# Main.net
KiCad netlist of a schematic drawn in Altium Designer
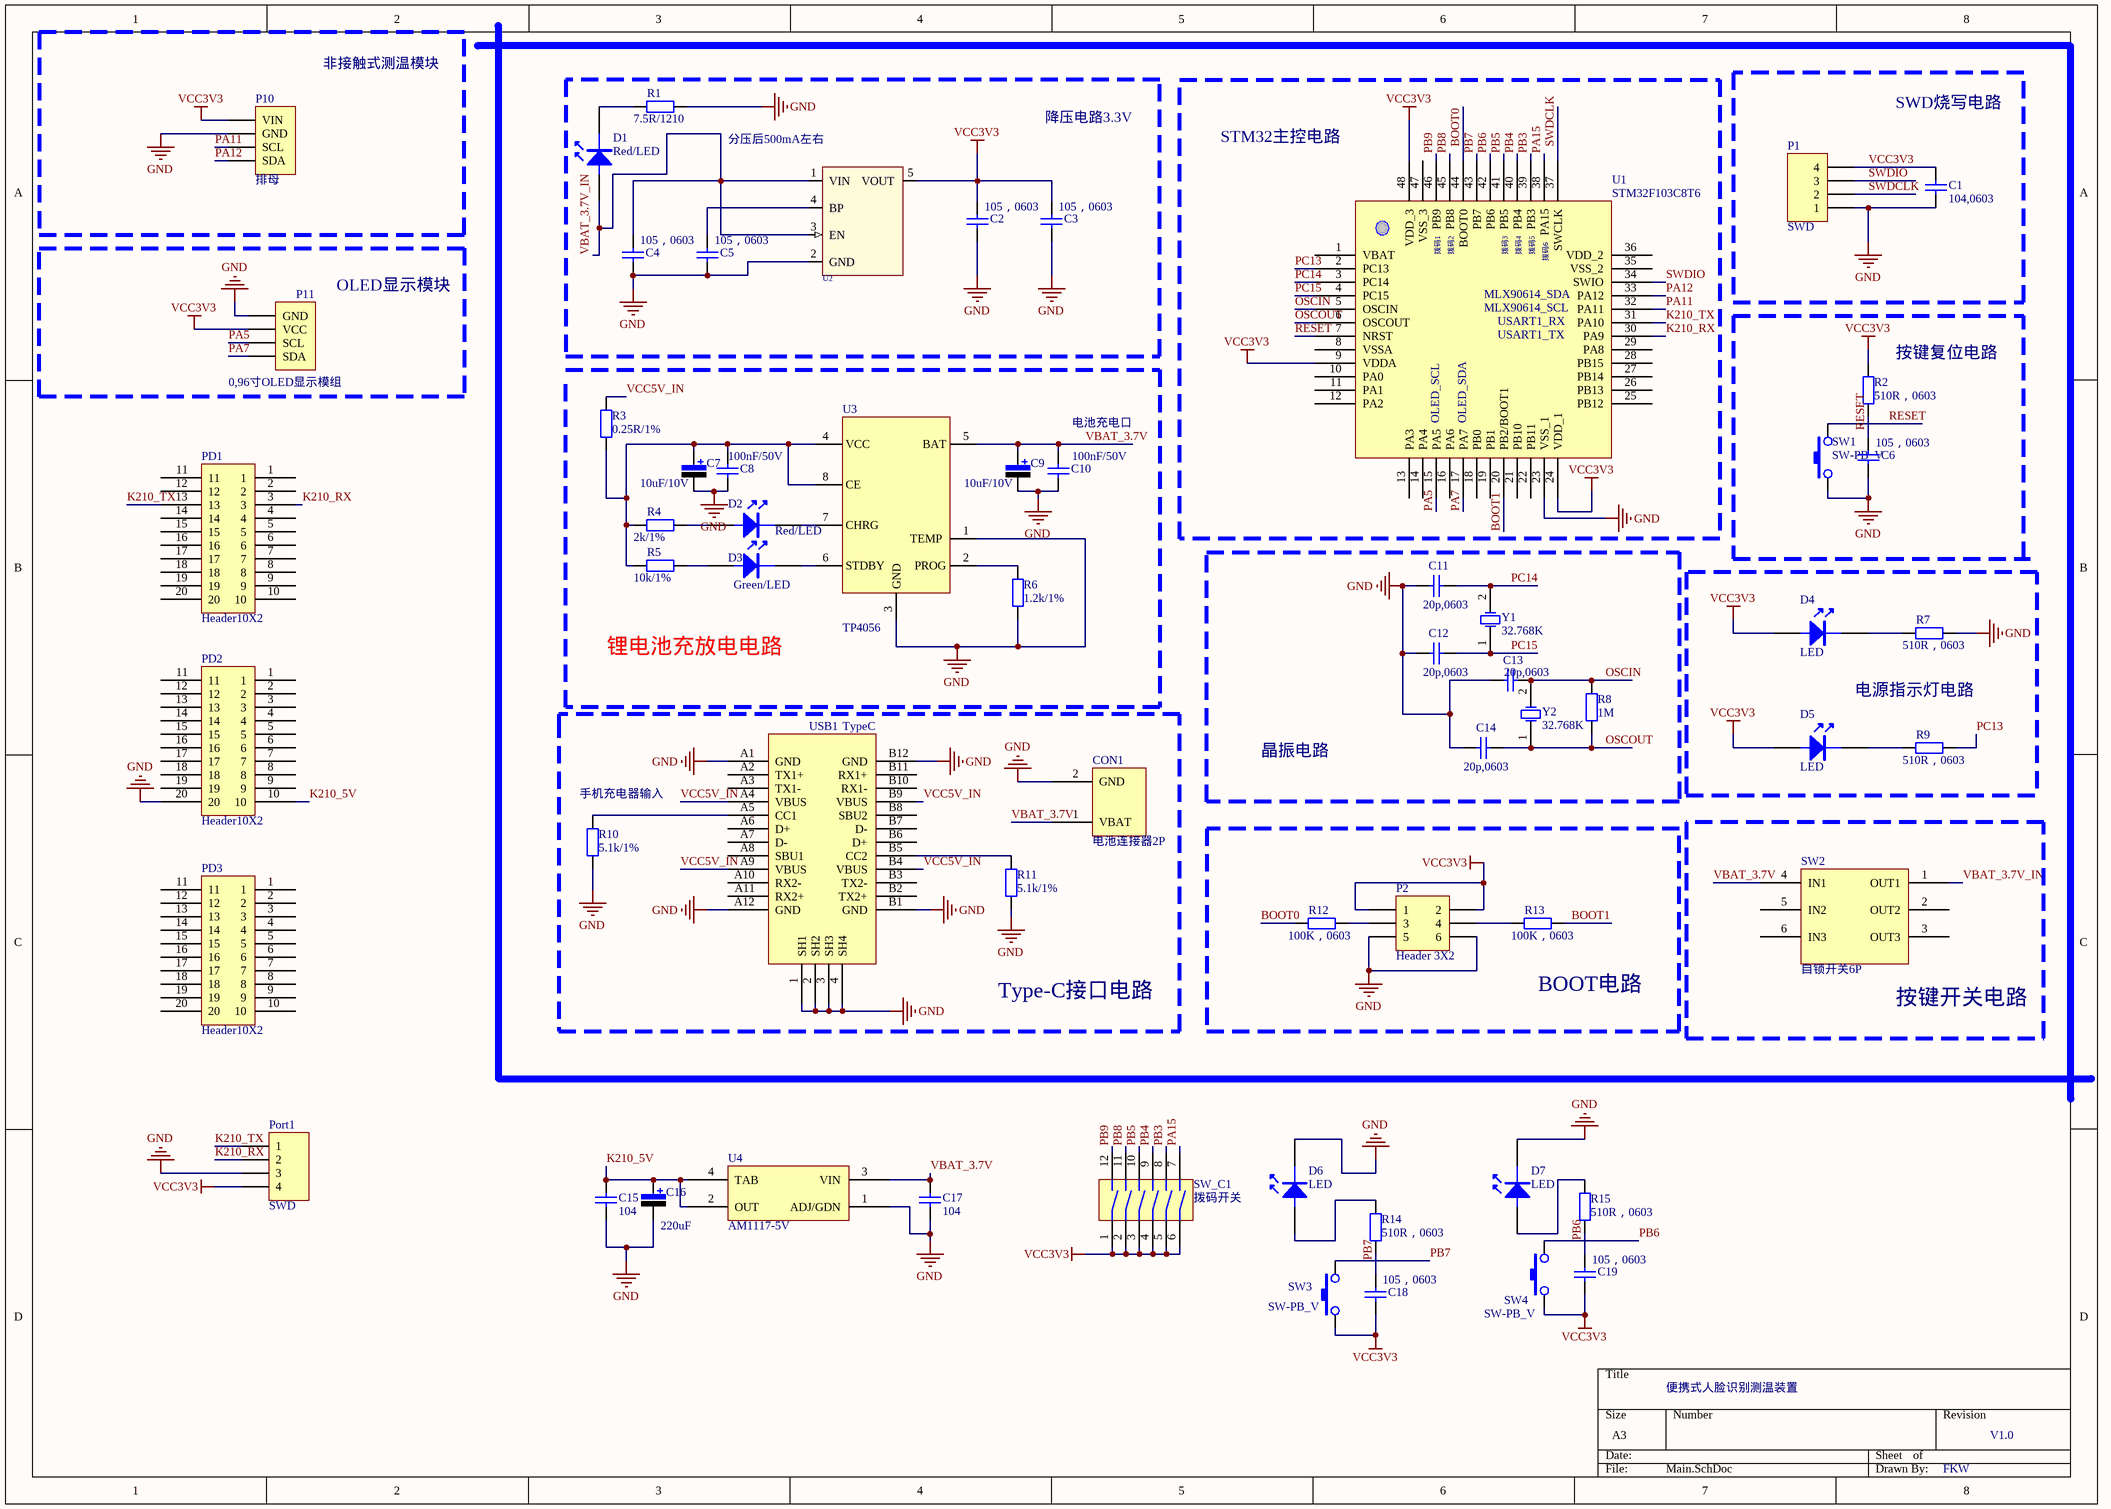
[diagram p0: Main.SchDoc]

(export (version "E")
  (design (tool "Eeschema 10.0.6"))
  (components
    (comp (ref "C1")
      (value "104,0603")
      (footprint "STM32F103C8T6核心板:C0603")
      (description "Capacitor")
      (fields (field (name "PUBLISHER") "Altium Limited"))
      (libsource (lib "STM32F103C8T6") (part "Cap"))
    )
    (comp (ref "C2")
      (value "105，0603")
      (footprint "STM32F103C8T6核心板:C0603")
      (description "Capacitor")
      (fields (field (name "PUBLISHER") "Altium Limited"))
      (libsource (lib "STM32F103C8T6") (part "Cap"))
    )
    (comp (ref "C3")
      (value "105，0603")
      (footprint "STM32F103C8T6核心板:C0603")
      (description "Capacitor")
      (fields (field (name "PUBLISHER") "Altium Limited"))
      (libsource (lib "STM32F103C8T6") (part "Cap"))
    )
    (comp (ref "C4")
      (value "105，0603")
      (footprint "STM32F103C8T6核心板:C0603")
      (description "Capacitor")
      (fields (field (name "PUBLISHER") "Altium Limited"))
      (libsource (lib "STM32F103C8T6") (part "Cap"))
    )
    (comp (ref "C5")
      (value "105，0603")
      (footprint "STM32F103C8T6核心板:C0603")
      (description "Capacitor")
      (fields (field (name "PUBLISHER") "Altium Limited"))
      (libsource (lib "STM32F103C8T6") (part "Cap"))
    )
    (comp (ref "C6")
      (value "105，0603")
      (footprint "STM32F103C8T6核心板:C0603")
      (description "Capacitor")
      (fields (field (name "PUBLISHER") "Altium Limited"))
      (libsource (lib "STM32F103C8T6") (part "Cap"))
    )
    (comp (ref "C7")
      (value "10uF/10V")
      (footprint "C0805tan")
      (libsource (lib "STM32F103C8T6") (part "Cap_电解电容"))
    )
    (comp (ref "C8")
      (value "100nF/50V")
      (footprint "STM32F103C8T6核心板:C0603")
      (description "Capacitor")
      (fields (field (name "PUBLISHER") "Altium Limited"))
      (libsource (lib "STM32F103C8T6") (part "Cap"))
    )
    (comp (ref "C9")
      (value "10uF/10V")
      (footprint "C0805tan")
      (libsource (lib "STM32F103C8T6") (part "Cap_电解电容"))
    )
    (comp (ref "C10")
      (value "100nF/50V")
      (footprint "STM32F103C8T6核心板:C0603")
      (description "Capacitor")
      (fields (field (name "PUBLISHER") "Altium Limited"))
      (libsource (lib "STM32F103C8T6") (part "Cap"))
    )
    (comp (ref "C11")
      (value "20p,0603")
      (footprint "STM32F103C8T6核心板:C0603")
      (description "Capacitor")
      (fields (field (name "PUBLISHER") "Altium Limited"))
      (libsource (lib "STM32F103C8T6") (part "Cap"))
    )
    (comp (ref "C12")
      (value "20p,0603")
      (footprint "STM32F103C8T6核心板:C0603")
      (description "Capacitor")
      (fields (field (name "PUBLISHER") "Altium Limited"))
      (libsource (lib "STM32F103C8T6") (part "Cap"))
    )
    (comp (ref "C13")
      (value "20p,0603")
      (footprint "STM32F103C8T6核心板:C0603")
      (description "Capacitor")
      (fields (field (name "PUBLISHER") "Altium Limited"))
      (libsource (lib "STM32F103C8T6") (part "Cap"))
    )
    (comp (ref "C14")
      (value "20p,0603")
      (footprint "STM32F103C8T6核心板:C0603")
      (description "Capacitor")
      (fields (field (name "PUBLISHER") "Altium Limited"))
      (libsource (lib "STM32F103C8T6") (part "Cap"))
    )
    (comp (ref "C15")
      (value "104")
      (footprint "STM32F103C8T6核心板:C0603")
      (description "Capacitor")
      (fields (field (name "PUBLISHER") "Altium Limited"))
      (libsource (lib "STM32F103C8T6") (part "Cap"))
    )
    (comp (ref "C16")
      (value "220uF")
      (footprint "C0805tan")
      (libsource (lib "STM32F103C8T6") (part "Cap_电解电容"))
    )
    (comp (ref "C17")
      (value "104")
      (footprint "STM32F103C8T6核心板:C0603")
      (description "Capacitor")
      (fields (field (name "PUBLISHER") "Altium Limited"))
      (libsource (lib "STM32F103C8T6") (part "Cap"))
    )
    (comp (ref "C18")
      (value "105，0603")
      (footprint "STM32F103C8T6核心板:C0603")
      (description "Capacitor")
      (fields (field (name "PUBLISHER") "Altium Limited"))
      (libsource (lib "STM32F103C8T6") (part "Cap"))
    )
    (comp (ref "C19")
      (value "105，0603")
      (footprint "STM32F103C8T6核心板:C0603")
      (description "Capacitor")
      (fields (field (name "PUBLISHER") "Altium Limited"))
      (libsource (lib "STM32F103C8T6") (part "Cap"))
    )
    (comp (ref "CON1")
      (value "电池连接器2P")
      (footprint "STM32F103C8T6核心板:CONN-TH_DF1B-2P-2.5DSA-01")
      (description "电池（带防呆口）")
      (libsource (lib "STM32F103C8T6") (part "BATinput_Connector"))
    )
    (comp (ref "D1") (value "Red/LED") (footprint "LED") (libsource (lib "STM32F103C8T6") (part "LED")))
    (comp (ref "D2") (value "Red/LED") (footprint "LED") (libsource (lib "STM32F103C8T6") (part "LED")))
    (comp (ref "D3") (value "Green/LED") (footprint "LED") (libsource (lib "STM32F103C8T6") (part "LED")))
    (comp (ref "D4") (value "LED") (footprint "LED") (libsource (lib "STM32F103C8T6") (part "LED")))
    (comp (ref "D5") (value "LED") (footprint "LED") (libsource (lib "STM32F103C8T6") (part "LED")))
    (comp (ref "D6") (value "LED") (footprint "LED") (libsource (lib "STM32F103C8T6") (part "LED")))
    (comp (ref "D7") (value "LED") (footprint "LED") (libsource (lib "STM32F103C8T6") (part "LED")))
    (comp (ref "P1")
      (value "SWD")
      (footprint "HDR1X4H")
      (description "Header, 4-Pin")
      (fields (field (name "PUBLISHER") "Altium Limited"))
      (libsource (lib "") (part "Header 4_1"))
    )
    (comp (ref "P2")
      (value "Header 3X2")
      (footprint "STM32F103C8T6核心板:HDR2X3")
      (description "Header, 3-Pin, Dual row")
      (fields (field (name "PUBLISHER") "Altium Limited"))
      (libsource (lib "STM32F103C8T6") (part "Header 3X2"))
    )
    (comp (ref "P10") (value "排母") (footprint "HRD1X4") (libsource (lib "STM32F103C8T6") (part "MLX90614")))
    (comp (ref "P11")
      (value "0,96寸OLED显示模组")
      (footprint "STM32F103C8T6核心板:0.96寸OLED显示模组")
      (libsource (lib "STM32F103C8T6") (part "0,96寸OLED显示模组"))
    )
    (comp (ref "PD1")
      (value "Header10X2")
      (footprint "header2X10")
      (libsource (lib "STM32F103C8T6") (part "Header10X2"))
    )
    (comp (ref "PD2")
      (value "Header10X2")
      (footprint "header2X10")
      (libsource (lib "STM32F103C8T6") (part "Header10X2"))
    )
    (comp (ref "PD3")
      (value "Header10X2")
      (footprint "header2X10")
      (libsource (lib "STM32F103C8T6") (part "Header10X2"))
    )
    (comp (ref "Port1")
      (value "SWD")
      (footprint "HDR1X4H")
      (description "Header, 4-Pin")
      (fields (field (name "PUBLISHER") "Altium Limited"))
      (libsource (lib "STM32F103C8T6") (part "Header 4"))
    )
    (comp (ref "R1")
      (value "7.5R/1210")
      (footprint "R0603")
      (description "Resistor")
      (fields (field (name "PUBLISHER") "Altium Limited"))
      (libsource (lib "STM32F103C8T6") (part "Res2"))
    )
    (comp (ref "R2")
      (value "510R，0603")
      (footprint "R0603")
      (description "Resistor")
      (fields (field (name "PUBLISHER") "Altium Limited"))
      (libsource (lib "") (part "Res2_1"))
    )
    (comp (ref "R3")
      (value "0.25R/1%")
      (footprint "R0603")
      (description "Resistor")
      (fields (field (name "PUBLISHER") "Altium Limited"))
      (libsource (lib "") (part "Res2_2"))
    )
    (comp (ref "R4")
      (value "2k/1%")
      (footprint "R0603")
      (description "Resistor")
      (fields (field (name "PUBLISHER") "Altium Limited"))
      (libsource (lib "STM32F103C8T6") (part "Res2"))
    )
    (comp (ref "R5")
      (value "10k/1%")
      (footprint "R0603")
      (description "Resistor")
      (fields (field (name "PUBLISHER") "Altium Limited"))
      (libsource (lib "STM32F103C8T6") (part "Res2"))
    )
    (comp (ref "R6")
      (value "1.2k/1%")
      (footprint "R0603")
      (description "Resistor")
      (fields (field (name "PUBLISHER") "Altium Limited"))
      (libsource (lib "") (part "Res2_2"))
    )
    (comp (ref "R7")
      (value "510R，0603")
      (footprint "R0603")
      (description "Resistor")
      (fields (field (name "PUBLISHER") "Altium Limited"))
      (libsource (lib "STM32F103C8T6") (part "Res2"))
    )
    (comp (ref "R8")
      (value "1M")
      (footprint "R0603")
      (description "Resistor")
      (fields (field (name "PUBLISHER") "Altium Limited"))
      (libsource (lib "") (part "Res2_1"))
    )
    (comp (ref "R9")
      (value "510R，0603")
      (footprint "R0603")
      (description "Resistor")
      (fields (field (name "PUBLISHER") "Altium Limited"))
      (libsource (lib "STM32F103C8T6") (part "Res2"))
    )
    (comp (ref "R10")
      (value "5.1k/1%")
      (footprint "R0603")
      (description "Resistor")
      (fields (field (name "PUBLISHER") "Altium Limited"))
      (libsource (lib "") (part "Res2_2"))
    )
    (comp (ref "R11")
      (value "5.1k/1%")
      (footprint "R0603")
      (description "Resistor")
      (fields (field (name "PUBLISHER") "Altium Limited"))
      (libsource (lib "") (part "Res2_2"))
    )
    (comp (ref "R12")
      (value "100K，0603")
      (footprint "R0603")
      (description "Resistor")
      (fields (field (name "PUBLISHER") "Altium Limited"))
      (libsource (lib "STM32F103C8T6") (part "Res2"))
    )
    (comp (ref "R13")
      (value "100K，0603")
      (footprint "R0603")
      (description "Resistor")
      (fields (field (name "PUBLISHER") "Altium Limited"))
      (libsource (lib "STM32F103C8T6") (part "Res2"))
    )
    (comp (ref "R14")
      (value "510R，0603")
      (footprint "R0603")
      (description "Resistor")
      (fields (field (name "PUBLISHER") "Altium Limited"))
      (libsource (lib "") (part "Res2_1"))
    )
    (comp (ref "R15")
      (value "510R，0603")
      (footprint "R0603")
      (description "Resistor")
      (fields (field (name "PUBLISHER") "Altium Limited"))
      (libsource (lib "") (part "Res2_1"))
    )
    (comp (ref "SW1")
      (value "SW-PB_V")
      (footprint "轻触开关_TPR_SMD")
      (description "SWITCH")
      (libsource (lib "STM32F103C8T6") (part "SW-PB_V"))
    )
    (comp (ref "SW2") (value "自锁开关6P") (footprint "SW_自锁") (libsource (lib "STM32F103C8T6") (part "SW-自锁6P")))
    (comp (ref "SW3")
      (value "SW-PB_V")
      (footprint "轻触开关_TPR_SMD")
      (description "SWITCH")
      (libsource (lib "STM32F103C8T6") (part "SW-PB_V"))
    )
    (comp (ref "SW4")
      (value "SW-PB_V")
      (footprint "轻触开关_TPR_SMD")
      (description "SWITCH")
      (libsource (lib "STM32F103C8T6") (part "SW-PB_V"))
    )
    (comp (ref "SW_C1") (value "拨码开关") (footprint "6P拨码开关") (libsource (lib "STM32F103C8T6") (part "拨码开关6P")))
    (comp (ref "U1")
      (value "STM32F103C8T6")
      (footprint "STM32F103C8T6核心板:48P")
      (libsource (lib "STM32F103C8T6") (part "STM32F103C8T6"))
    )
    (comp (ref "U2")
      (value "RT9193")
      (fields (field (name "ICA_PARTNUM") "$$2191094$$RT9193-15CU5") (field (name "PART NUMBER") "TMP-13"))
      (libsource (lib "STM32F103C8T6") (part "RT9193X_5P"))
    )
    (comp (ref "U3")
      (value "TP4056")
      (footprint "STM32F103C8T6核心板:SOP8-TP4056-3D")
      (description "锂电池充放电芯片")
      (libsource (lib "STM32F103C8T6") (part "TP4056"))
    )
    (comp (ref "U4")
      (value "AM1117-5V")
      (footprint "AM1117-5V-SOT-223")
      (description "低压差线性稳压器")
      (libsource (lib "STM32F103C8T6") (part "AM1117-5V"))
    )
    (comp (ref "USB1")
      (value "TypeC")
      (footprint "STM32F103C8T6核心板:Type-c")
      (libsource (lib "STM32F103C8T6") (part "USB-Type-C"))
    )
    (comp (ref "Y1")
      (value "32.768K")
      (footprint "SMD2012")
      (description "Crystal Oscillator")
      (fields (field (name "PUBLISHER") "Altium Limited"))
      (libsource (lib "STM32F103C8T6") (part "XTAL"))
    )
    (comp (ref "Y2")
      (value "32.768K")
      (footprint "STM32F103C8T6核心板:XTAL1")
      (description "Crystal Oscillator")
      (fields (field (name "PUBLISHER") "Altium Limited"))
      (libsource (lib "STM32F103C8T6") (part "XTAL"))
    )
  )
  (nets
    (net (code "1") (name "/BOOT0") (class "Default")
      (node (ref "R12") (pin "2") (pinfunction "2_2") (pintype "passive"))
      (node (ref "U1") (pin "44") (pinfunction "BOOT0_44") (pintype "passive"))
    )
    (net (code "2") (name "/BOOT1") (class "Default")
      (node (ref "R13") (pin "1") (pinfunction "1_1") (pintype "passive"))
      (node (ref "U1") (pin "20") (pinfunction "PB2/BOOT1_20") (pintype "passive"))
    )
    (net (code "3") (name "/K210_5V") (class "Default")
      (node (ref "C15") (pin "2") (pinfunction "2_2") (pintype "passive"))
      (node (ref "C16") (pin "1") (pinfunction "1_1") (pintype "passive"))
      (node (ref "PD2") (pin "10") (pinfunction "10_10") (pintype "passive"))
      (node (ref "U4") (pin "2") (pinfunction "OUT_2") (pintype "passive"))
      (node (ref "U4") (pin "4") (pinfunction "TAB_4") (pintype "passive"))
    )
    (net (code "4") (name "/K210_RX") (class "Default")
      (node (ref "PD1") (pin "3") (pinfunction "3_3") (pintype "passive"))
      (node (ref "Port1") (pin "2") (pinfunction "2_2") (pintype "passive"))
      (node (ref "U1") (pin "30") (pinfunction "PA9_30") (pintype "passive"))
    )
    (net (code "5") (name "/K210_TX") (class "Default")
      (node (ref "PD1") (pin "13") (pinfunction "13_13") (pintype "passive"))
      (node (ref "Port1") (pin "1") (pinfunction "1_1") (pintype "passive"))
      (node (ref "U1") (pin "31") (pinfunction "PA10_31") (pintype "passive"))
    )
    (net (code "6") (name "/OSCIN") (class "Default")
      (node (ref "C13") (pin "2") (pinfunction "2_2") (pintype "passive"))
      (node (ref "R8") (pin "2") (pinfunction "2_2") (pintype "passive"))
      (node (ref "U1") (pin "5") (pinfunction "OSCIN_5") (pintype "passive"))
      (node (ref "Y2") (pin "2") (pinfunction "OSC2_2") (pintype "passive"))
    )
    (net (code "7") (name "/OSCOUT") (class "Default")
      (node (ref "C14") (pin "2") (pinfunction "2_2") (pintype "passive"))
      (node (ref "R8") (pin "1") (pinfunction "1_1") (pintype "passive"))
      (node (ref "U1") (pin "6") (pinfunction "OSCOUT_6") (pintype "passive"))
      (node (ref "Y2") (pin "1") (pinfunction "OSC1_1") (pintype "passive"))
    )
    (net (code "8") (name "/PA5") (class "Default")
      (node (ref "P11") (pin "3") (pinfunction "SCL_3") (pintype "passive"))
      (node (ref "U1") (pin "15") (pinfunction "PA5_15") (pintype "passive"))
    )
    (net (code "9") (name "/PA7") (class "Default")
      (node (ref "P11") (pin "4") (pinfunction "SDA_4") (pintype "passive"))
      (node (ref "U1") (pin "17") (pinfunction "PA7_17") (pintype "passive"))
    )
    (net (code "10") (name "/PA11") (class "Default")
      (node (ref "P10") (pin "3") (pinfunction "SCL_3") (pintype "passive"))
      (node (ref "U1") (pin "32") (pinfunction "PA11_32") (pintype "passive"))
    )
    (net (code "11") (name "/PA12") (class "Default")
      (node (ref "P10") (pin "4") (pinfunction "SDA_4") (pintype "passive"))
      (node (ref "U1") (pin "33") (pinfunction "PA12_33") (pintype "passive"))
    )
    (net (code "12") (name "/PA15") (class "Default")
      (node (ref "SW_C1") (pin "7") (pinfunction "7_7") (pintype "passive"))
      (node (ref "U1") (pin "38") (pinfunction "PA15_38") (pintype "passive"))
    )
    (net (code "13") (name "/PB3") (class "Default")
      (node (ref "SW_C1") (pin "8") (pinfunction "8_8") (pintype "passive"))
      (node (ref "U1") (pin "39") (pinfunction "PB3_39") (pintype "passive"))
    )
    (net (code "14") (name "/PB4") (class "Default")
      (node (ref "SW_C1") (pin "9") (pinfunction "9_9") (pintype "passive"))
      (node (ref "U1") (pin "40") (pinfunction "PB4_40") (pintype "passive"))
    )
    (net (code "15") (name "/PB5") (class "Default")
      (node (ref "SW_C1") (pin "10") (pinfunction "10_10") (pintype "passive"))
      (node (ref "U1") (pin "41") (pinfunction "PB5_41") (pintype "passive"))
    )
    (net (code "16") (name "/PB6") (class "Default")
      (node (ref "C19") (pin "2") (pinfunction "2_2") (pintype "passive"))
      (node (ref "R15") (pin "1") (pinfunction "1_1") (pintype "passive"))
      (node (ref "SW4") (pin "2") (pinfunction "2_2") (pintype "passive"))
      (node (ref "U1") (pin "42") (pinfunction "PB6_42") (pintype "passive"))
    )
    (net (code "17") (name "/PB7") (class "Default")
      (node (ref "C18") (pin "2") (pinfunction "2_2") (pintype "passive"))
      (node (ref "R14") (pin "1") (pinfunction "1_1") (pintype "passive"))
      (node (ref "SW3") (pin "2") (pinfunction "2_2") (pintype "passive"))
      (node (ref "U1") (pin "43") (pinfunction "PB7_43") (pintype "passive"))
    )
    (net (code "18") (name "/PB8") (class "Default")
      (node (ref "SW_C1") (pin "11") (pinfunction "11_11") (pintype "passive"))
      (node (ref "U1") (pin "45") (pinfunction "PB8_45") (pintype "passive"))
    )
    (net (code "19") (name "/PB9") (class "Default")
      (node (ref "SW_C1") (pin "12") (pinfunction "12_12") (pintype "passive"))
      (node (ref "U1") (pin "46") (pinfunction "PB9_46") (pintype "passive"))
    )
    (net (code "20") (name "/PC13") (class "Default")
      (node (ref "R9") (pin "1") (pinfunction "1_1") (pintype "passive"))
      (node (ref "U1") (pin "2") (pinfunction "PC13_2") (pintype "passive"))
    )
    (net (code "21") (name "/PC14") (class "Default")
      (node (ref "C11") (pin "2") (pinfunction "2_2") (pintype "passive"))
      (node (ref "U1") (pin "3") (pinfunction "PC14_3") (pintype "passive"))
      (node (ref "Y1") (pin "2") (pinfunction "OSC2_2") (pintype "passive"))
    )
    (net (code "22") (name "/PC15") (class "Default")
      (node (ref "C12") (pin "2") (pinfunction "2_2") (pintype "passive"))
      (node (ref "U1") (pin "4") (pinfunction "PC15_4") (pintype "passive"))
      (node (ref "Y1") (pin "1") (pinfunction "OSC1_1") (pintype "passive"))
    )
    (net (code "23") (name "/RESET") (class "Default")
      (node (ref "C6") (pin "2") (pinfunction "2_2") (pintype "passive"))
      (node (ref "R2") (pin "1") (pinfunction "1_1") (pintype "passive"))
      (node (ref "SW1") (pin "2") (pinfunction "2_2") (pintype "passive"))
      (node (ref "U1") (pin "7") (pinfunction "NRST_7") (pintype "passive"))
    )
    (net (code "24") (name "/SWDCLK") (class "Default")
      (node (ref "P1") (pin "2") (pinfunction "2_2") (pintype "passive"))
      (node (ref "U1") (pin "37") (pinfunction "SWCLK_37") (pintype "passive"))
    )
    (net (code "25") (name "/SWDIO") (class "Default")
      (node (ref "P1") (pin "3") (pinfunction "3_3") (pintype "passive"))
      (node (ref "U1") (pin "34") (pinfunction "SWIO_34") (pintype "passive"))
    )
    (net (code "26") (name "/VBAT_3.7V") (class "Default")
      (node (ref "C10") (pin "2") (pinfunction "2_2") (pintype "passive"))
      (node (ref "C17") (pin "2") (pinfunction "2_2") (pintype "passive"))
      (node (ref "C9") (pin "1") (pinfunction "1_1") (pintype "passive"))
      (node (ref "CON1") (pin "1") (pinfunction "VBAT_1") (pintype "passive"))
      (node (ref "SW2") (pin "4") (pinfunction "IN1_4") (pintype "passive"))
      (node (ref "U3") (pin "5") (pinfunction "BAT_5") (pintype "passive"))
      (node (ref "U4") (pin "3") (pinfunction "VIN_3") (pintype "passive"))
    )
    (net (code "27") (name "/VBAT_3.7V_IN") (class "Default")
      (node (ref "C4") (pin "2") (pinfunction "2_2") (pintype "passive"))
      (node (ref "D1") (pin "A") (pinfunction "1_A") (pintype "passive"))
      (node (ref "SW2") (pin "1") (pinfunction "OUT1_1") (pintype "passive"))
      (node (ref "U2") (pin "1") (pinfunction "VIN_1") (pintype "power_in"))
      (node (ref "U2") (pin "3") (pinfunction "EN_3") (pintype "input"))
    )
    (net (code "28") (name "/VCC5V_IN") (class "Default")
      (node (ref "R3") (pin "1") (pinfunction "1_1") (pintype "passive"))
      (node (ref "USB1") (pin "A4") (pinfunction "VBUS_A4") (pintype "passive"))
      (node (ref "USB1") (pin "A9") (pinfunction "VBUS_A9") (pintype "passive"))
      (node (ref "USB1") (pin "B4") (pinfunction "VBUS_B4") (pintype "passive"))
      (node (ref "USB1") (pin "B9") (pinfunction "VBUS_B9") (pintype "passive"))
    )
    (net (code "29") (name "GND") (class "Default")
      (node (ref "C1") (pin "1") (pinfunction "1_1") (pintype "passive"))
      (node (ref "C10") (pin "1") (pinfunction "1_1") (pintype "passive"))
      (node (ref "C11") (pin "1") (pinfunction "1_1") (pintype "passive"))
      (node (ref "C12") (pin "1") (pinfunction "1_1") (pintype "passive"))
      (node (ref "C13") (pin "1") (pinfunction "1_1") (pintype "passive"))
      (node (ref "C14") (pin "1") (pinfunction "1_1") (pintype "passive"))
      (node (ref "C15") (pin "1") (pinfunction "1_1") (pintype "passive"))
      (node (ref "C16") (pin "2") (pinfunction "2_2") (pintype "passive"))
      (node (ref "C17") (pin "1") (pinfunction "1_1") (pintype "passive"))
      (node (ref "C2") (pin "1") (pinfunction "1_1") (pintype "passive"))
      (node (ref "C3") (pin "1") (pinfunction "1_1") (pintype "passive"))
      (node (ref "C4") (pin "1") (pinfunction "1_1") (pintype "passive"))
      (node (ref "C5") (pin "1") (pinfunction "1_1") (pintype "passive"))
      (node (ref "C6") (pin "1") (pinfunction "1_1") (pintype "passive"))
      (node (ref "C7") (pin "2") (pinfunction "2_2") (pintype "passive"))
      (node (ref "C8") (pin "1") (pinfunction "1_1") (pintype "passive"))
      (node (ref "C9") (pin "2") (pinfunction "2_2") (pintype "passive"))
      (node (ref "CON1") (pin "2") (pinfunction "GND_2") (pintype "passive"))
      (node (ref "D6") (pin "K") (pinfunction "2_K") (pintype "passive"))
      (node (ref "D7") (pin "K") (pinfunction "2_K") (pintype "passive"))
      (node (ref "P1") (pin "1") (pinfunction "1_1") (pintype "passive"))
      (node (ref "P10") (pin "2") (pinfunction "GND_2") (pintype "passive"))
      (node (ref "P11") (pin "1") (pinfunction "GND_1") (pintype "passive"))
      (node (ref "P2") (pin "5") (pinfunction "5_5") (pintype "passive"))
      (node (ref "P2") (pin "6") (pinfunction "6_6") (pintype "passive"))
      (node (ref "PD2") (pin "20") (pinfunction "20_20") (pintype "passive"))
      (node (ref "Port1") (pin "3") (pinfunction "3_3") (pintype "passive"))
      (node (ref "R1") (pin "1") (pinfunction "1_1") (pintype "passive"))
      (node (ref "R10") (pin "2") (pinfunction "2_2") (pintype "passive"))
      (node (ref "R11") (pin "2") (pinfunction "2_2") (pintype "passive"))
      (node (ref "R6") (pin "2") (pinfunction "2_2") (pintype "passive"))
      (node (ref "R7") (pin "1") (pinfunction "1_1") (pintype "passive"))
      (node (ref "SW1") (pin "1") (pinfunction "1_1") (pintype "passive"))
      (node (ref "U1") (pin "23") (pinfunction "VSS_1_23") (pintype "passive"))
      (node (ref "U2") (pin "2") (pinfunction "GND_2") (pintype "power_in"))
      (node (ref "U3") (pin "1") (pinfunction "TEMP_1") (pintype "passive"))
      (node (ref "U3") (pin "3") (pinfunction "GND_3") (pintype "passive"))
      (node (ref "U4") (pin "1") (pinfunction "ADJ/GDN_1") (pintype "passive"))
      (node (ref "USB1") (pin "1") (pinfunction "SH1_1") (pintype "passive"))
      (node (ref "USB1") (pin "2") (pinfunction "SH2_2") (pintype "passive"))
      (node (ref "USB1") (pin "3") (pinfunction "SH3_3") (pintype "passive"))
      (node (ref "USB1") (pin "4") (pinfunction "SH4_4") (pintype "passive"))
      (node (ref "USB1") (pin "A1") (pinfunction "GND_A1") (pintype "passive"))
      (node (ref "USB1") (pin "A12") (pinfunction "GND_A12") (pintype "passive"))
      (node (ref "USB1") (pin "B1") (pinfunction "GND_B1") (pintype "passive"))
      (node (ref "USB1") (pin "B12") (pinfunction "GND_B12") (pintype "passive"))
    )
    (net (code "30") (name "Net-(D1-2)") (class "Default")
      (node (ref "D1") (pin "K") (pinfunction "2_K") (pintype "passive"))
      (node (ref "R1") (pin "2") (pinfunction "2_2") (pintype "passive"))
    )
    (net (code "31") (name "Net-(D2-1)") (class "Default")
      (node (ref "D2") (pin "A") (pinfunction "1_A") (pintype "passive"))
      (node (ref "R4") (pin "1") (pinfunction "1_1") (pintype "passive"))
    )
    (net (code "32") (name "Net-(D2-2)") (class "Default")
      (node (ref "D2") (pin "K") (pinfunction "2_K") (pintype "passive"))
      (node (ref "U3") (pin "7") (pinfunction "CHRG_7") (pintype "passive"))
    )
    (net (code "33") (name "Net-(D3-1)") (class "Default")
      (node (ref "D3") (pin "A") (pinfunction "1_A") (pintype "passive"))
      (node (ref "R5") (pin "1") (pinfunction "1_1") (pintype "passive"))
    )
    (net (code "34") (name "Net-(D3-2)") (class "Default")
      (node (ref "D3") (pin "K") (pinfunction "2_K") (pintype "passive"))
      (node (ref "U3") (pin "6") (pinfunction "STDBY_6") (pintype "passive"))
    )
    (net (code "35") (name "Net-(D4-2)") (class "Default")
      (node (ref "D4") (pin "K") (pinfunction "2_K") (pintype "passive"))
      (node (ref "R7") (pin "2") (pinfunction "2_2") (pintype "passive"))
    )
    (net (code "36") (name "Net-(D5-2)") (class "Default")
      (node (ref "D5") (pin "K") (pinfunction "2_K") (pintype "passive"))
      (node (ref "R9") (pin "2") (pinfunction "2_2") (pintype "passive"))
    )
    (net (code "37") (name "Net-(D6-1)") (class "Default")
      (node (ref "D6") (pin "A") (pinfunction "1_A") (pintype "passive"))
      (node (ref "R14") (pin "2") (pinfunction "2_2") (pintype "passive"))
    )
    (net (code "38") (name "Net-(D7-1)") (class "Default")
      (node (ref "D7") (pin "A") (pinfunction "1_A") (pintype "passive"))
      (node (ref "R15") (pin "2") (pinfunction "2_2") (pintype "passive"))
    )
    (net (code "39") (name "Net-(P2-Pad3)") (class "Default")
      (node (ref "P2") (pin "3") (pinfunction "3_3") (pintype "passive"))
      (node (ref "R12") (pin "1") (pinfunction "1_1") (pintype "passive"))
    )
    (net (code "40") (name "Net-(P2-Pad4)") (class "Default")
      (node (ref "P2") (pin "4") (pinfunction "4_4") (pintype "passive"))
      (node (ref "R13") (pin "2") (pinfunction "2_2") (pintype "passive"))
    )
    (net (code "41") (name "Net-(U2-BP)") (class "Default")
      (node (ref "C5") (pin "2") (pinfunction "2_2") (pintype "passive"))
      (node (ref "U2") (pin "4") (pinfunction "BP_4") (pintype "passive"))
    )
    (net (code "42") (name "Net-(U3-CE)") (class "Default")
      (node (ref "C7") (pin "1") (pinfunction "1_1") (pintype "passive"))
      (node (ref "C8") (pin "2") (pinfunction "2_2") (pintype "passive"))
      (node (ref "R3") (pin "2") (pinfunction "2_2") (pintype "passive"))
      (node (ref "R4") (pin "2") (pinfunction "2_2") (pintype "passive"))
      (node (ref "R5") (pin "2") (pinfunction "2_2") (pintype "passive"))
      (node (ref "U3") (pin "4") (pinfunction "VCC_4") (pintype "passive"))
      (node (ref "U3") (pin "8") (pinfunction "CE_8") (pintype "passive"))
    )
    (net (code "43") (name "Net-(U3-PROG)") (class "Default")
      (node (ref "R6") (pin "1") (pinfunction "1_1") (pintype "passive"))
      (node (ref "U3") (pin "2") (pinfunction "PROG_2") (pintype "passive"))
    )
    (net (code "44") (name "Net-(USB1-CC1)") (class "Default")
      (node (ref "R10") (pin "1") (pinfunction "1_1") (pintype "passive"))
      (node (ref "USB1") (pin "A5") (pinfunction "CC1_A5") (pintype "passive"))
    )
    (net (code "45") (name "Net-(USB1-CC2)") (class "Default")
      (node (ref "R11") (pin "1") (pinfunction "1_1") (pintype "passive"))
      (node (ref "USB1") (pin "B5") (pinfunction "CC2_B5") (pintype "passive"))
    )
    (net (code "46") (name "VCC3V3") (class "Default")
      (node (ref "C1") (pin "2") (pinfunction "2_2") (pintype "passive"))
      (node (ref "C18") (pin "1") (pinfunction "1_1") (pintype "passive"))
      (node (ref "C19") (pin "1") (pinfunction "1_1") (pintype "passive"))
      (node (ref "C2") (pin "2") (pinfunction "2_2") (pintype "passive"))
      (node (ref "C3") (pin "2") (pinfunction "2_2") (pintype "passive"))
      (node (ref "D4") (pin "A") (pinfunction "1_A") (pintype "passive"))
      (node (ref "D5") (pin "A") (pinfunction "1_A") (pintype "passive"))
      (node (ref "P1") (pin "4") (pinfunction "4_4") (pintype "passive"))
      (node (ref "P10") (pin "1") (pinfunction "VIN_1") (pintype "passive"))
      (node (ref "P11") (pin "2") (pinfunction "VCC_2") (pintype "passive"))
      (node (ref "P2") (pin "1") (pinfunction "1_1") (pintype "passive"))
      (node (ref "P2") (pin "2") (pinfunction "2_2") (pintype "passive"))
      (node (ref "Port1") (pin "4") (pinfunction "4_4") (pintype "passive"))
      (node (ref "R2") (pin "2") (pinfunction "2_2") (pintype "passive"))
      (node (ref "SW3") (pin "1") (pinfunction "1_1") (pintype "passive"))
      (node (ref "SW4") (pin "1") (pinfunction "1_1") (pintype "passive"))
      (node (ref "SW_C1") (pin "1") (pinfunction "1_1") (pintype "passive"))
      (node (ref "SW_C1") (pin "2") (pinfunction "2_2") (pintype "passive"))
      (node (ref "SW_C1") (pin "3") (pinfunction "3_3") (pintype "passive"))
      (node (ref "SW_C1") (pin "4") (pinfunction "4_4") (pintype "passive"))
      (node (ref "SW_C1") (pin "5") (pinfunction "5_5") (pintype "passive"))
      (node (ref "SW_C1") (pin "6") (pinfunction "6_6") (pintype "passive"))
      (node (ref "U1") (pin "24") (pinfunction "VDD_1_24") (pintype "passive"))
      (node (ref "U1") (pin "48") (pinfunction "VDD_3_48") (pintype "passive"))
      (node (ref "U1") (pin "9") (pinfunction "VDDA_9") (pintype "passive"))
      (node (ref "U2") (pin "5") (pinfunction "VOUT_5") (pintype "power_in"))
    )
    (net (code "47") (name "unconnected-(PD1-Pad1)") (class "Default")
      (node (ref "PD1") (pin "1") (pinfunction "1_1") (pintype "passive"))
    )
    (net (code "48") (name "unconnected-(PD1-Pad2)") (class "Default")
      (node (ref "PD1") (pin "2") (pinfunction "2_2") (pintype "passive"))
    )
    (net (code "49") (name "unconnected-(PD1-Pad4)") (class "Default")
      (node (ref "PD1") (pin "4") (pinfunction "4_4") (pintype "passive"))
    )
    (net (code "50") (name "unconnected-(PD1-Pad5)") (class "Default")
      (node (ref "PD1") (pin "5") (pinfunction "5_5") (pintype "passive"))
    )
    (net (code "51") (name "unconnected-(PD1-Pad6)") (class "Default")
      (node (ref "PD1") (pin "6") (pinfunction "6_6") (pintype "passive"))
    )
    (net (code "52") (name "unconnected-(PD1-Pad7)") (class "Default")
      (node (ref "PD1") (pin "7") (pinfunction "7_7") (pintype "passive"))
    )
    (net (code "53") (name "unconnected-(PD1-Pad8)") (class "Default")
      (node (ref "PD1") (pin "8") (pinfunction "8_8") (pintype "passive"))
    )
    (net (code "54") (name "unconnected-(PD1-Pad9)") (class "Default")
      (node (ref "PD1") (pin "9") (pinfunction "9_9") (pintype "passive"))
    )
    (net (code "55") (name "unconnected-(PD1-Pad10)") (class "Default")
      (node (ref "PD1") (pin "10") (pinfunction "10_10") (pintype "passive"))
    )
    (net (code "56") (name "unconnected-(PD1-Pad11)") (class "Default")
      (node (ref "PD1") (pin "11") (pinfunction "11_11") (pintype "passive"))
    )
    (net (code "57") (name "unconnected-(PD1-Pad12)") (class "Default")
      (node (ref "PD1") (pin "12") (pinfunction "12_12") (pintype "passive"))
    )
    (net (code "58") (name "unconnected-(PD1-Pad14)") (class "Default")
      (node (ref "PD1") (pin "14") (pinfunction "14_14") (pintype "passive"))
    )
    (net (code "59") (name "unconnected-(PD1-Pad15)") (class "Default")
      (node (ref "PD1") (pin "15") (pinfunction "15_15") (pintype "passive"))
    )
    (net (code "60") (name "unconnected-(PD1-Pad16)") (class "Default")
      (node (ref "PD1") (pin "16") (pinfunction "16_16") (pintype "passive"))
    )
    (net (code "61") (name "unconnected-(PD1-Pad17)") (class "Default")
      (node (ref "PD1") (pin "17") (pinfunction "17_17") (pintype "passive"))
    )
    (net (code "62") (name "unconnected-(PD1-Pad18)") (class "Default")
      (node (ref "PD1") (pin "18") (pinfunction "18_18") (pintype "passive"))
    )
    (net (code "63") (name "unconnected-(PD1-Pad19)") (class "Default")
      (node (ref "PD1") (pin "19") (pinfunction "19_19") (pintype "passive"))
    )
    (net (code "64") (name "unconnected-(PD1-Pad20)") (class "Default")
      (node (ref "PD1") (pin "20") (pinfunction "20_20") (pintype "passive"))
    )
    (net (code "65") (name "unconnected-(PD2-Pad1)") (class "Default")
      (node (ref "PD2") (pin "1") (pinfunction "1_1") (pintype "passive"))
    )
    (net (code "66") (name "unconnected-(PD2-Pad2)") (class "Default")
      (node (ref "PD2") (pin "2") (pinfunction "2_2") (pintype "passive"))
    )
    (net (code "67") (name "unconnected-(PD2-Pad3)") (class "Default")
      (node (ref "PD2") (pin "3") (pinfunction "3_3") (pintype "passive"))
    )
    (net (code "68") (name "unconnected-(PD2-Pad4)") (class "Default")
      (node (ref "PD2") (pin "4") (pinfunction "4_4") (pintype "passive"))
    )
    (net (code "69") (name "unconnected-(PD2-Pad5)") (class "Default")
      (node (ref "PD2") (pin "5") (pinfunction "5_5") (pintype "passive"))
    )
    (net (code "70") (name "unconnected-(PD2-Pad6)") (class "Default")
      (node (ref "PD2") (pin "6") (pinfunction "6_6") (pintype "passive"))
    )
    (net (code "71") (name "unconnected-(PD2-Pad7)") (class "Default")
      (node (ref "PD2") (pin "7") (pinfunction "7_7") (pintype "passive"))
    )
    (net (code "72") (name "unconnected-(PD2-Pad8)") (class "Default")
      (node (ref "PD2") (pin "8") (pinfunction "8_8") (pintype "passive"))
    )
    (net (code "73") (name "unconnected-(PD2-Pad9)") (class "Default")
      (node (ref "PD2") (pin "9") (pinfunction "9_9") (pintype "passive"))
    )
    (net (code "74") (name "unconnected-(PD2-Pad11)") (class "Default")
      (node (ref "PD2") (pin "11") (pinfunction "11_11") (pintype "passive"))
    )
    (net (code "75") (name "unconnected-(PD2-Pad12)") (class "Default")
      (node (ref "PD2") (pin "12") (pinfunction "12_12") (pintype "passive"))
    )
    (net (code "76") (name "unconnected-(PD2-Pad13)") (class "Default")
      (node (ref "PD2") (pin "13") (pinfunction "13_13") (pintype "passive"))
    )
    (net (code "77") (name "unconnected-(PD2-Pad14)") (class "Default")
      (node (ref "PD2") (pin "14") (pinfunction "14_14") (pintype "passive"))
    )
    (net (code "78") (name "unconnected-(PD2-Pad15)") (class "Default")
      (node (ref "PD2") (pin "15") (pinfunction "15_15") (pintype "passive"))
    )
    (net (code "79") (name "unconnected-(PD2-Pad16)") (class "Default")
      (node (ref "PD2") (pin "16") (pinfunction "16_16") (pintype "passive"))
    )
    (net (code "80") (name "unconnected-(PD2-Pad17)") (class "Default")
      (node (ref "PD2") (pin "17") (pinfunction "17_17") (pintype "passive"))
    )
    (net (code "81") (name "unconnected-(PD2-Pad18)") (class "Default")
      (node (ref "PD2") (pin "18") (pinfunction "18_18") (pintype "passive"))
    )
    (net (code "82") (name "unconnected-(PD2-Pad19)") (class "Default")
      (node (ref "PD2") (pin "19") (pinfunction "19_19") (pintype "passive"))
    )
    (net (code "83") (name "unconnected-(PD3-Pad1)") (class "Default")
      (node (ref "PD3") (pin "1") (pinfunction "1_1") (pintype "passive"))
    )
    (net (code "84") (name "unconnected-(PD3-Pad2)") (class "Default")
      (node (ref "PD3") (pin "2") (pinfunction "2_2") (pintype "passive"))
    )
    (net (code "85") (name "unconnected-(PD3-Pad3)") (class "Default")
      (node (ref "PD3") (pin "3") (pinfunction "3_3") (pintype "passive"))
    )
    (net (code "86") (name "unconnected-(PD3-Pad4)") (class "Default")
      (node (ref "PD3") (pin "4") (pinfunction "4_4") (pintype "passive"))
    )
    (net (code "87") (name "unconnected-(PD3-Pad5)") (class "Default")
      (node (ref "PD3") (pin "5") (pinfunction "5_5") (pintype "passive"))
    )
    (net (code "88") (name "unconnected-(PD3-Pad6)") (class "Default")
      (node (ref "PD3") (pin "6") (pinfunction "6_6") (pintype "passive"))
    )
    (net (code "89") (name "unconnected-(PD3-Pad7)") (class "Default")
      (node (ref "PD3") (pin "7") (pinfunction "7_7") (pintype "passive"))
    )
    (net (code "90") (name "unconnected-(PD3-Pad8)") (class "Default")
      (node (ref "PD3") (pin "8") (pinfunction "8_8") (pintype "passive"))
    )
    (net (code "91") (name "unconnected-(PD3-Pad9)") (class "Default")
      (node (ref "PD3") (pin "9") (pinfunction "9_9") (pintype "passive"))
    )
    (net (code "92") (name "unconnected-(PD3-Pad10)") (class "Default")
      (node (ref "PD3") (pin "10") (pinfunction "10_10") (pintype "passive"))
    )
    (net (code "93") (name "unconnected-(PD3-Pad11)") (class "Default")
      (node (ref "PD3") (pin "11") (pinfunction "11_11") (pintype "passive"))
    )
    (net (code "94") (name "unconnected-(PD3-Pad12)") (class "Default")
      (node (ref "PD3") (pin "12") (pinfunction "12_12") (pintype "passive"))
    )
    (net (code "95") (name "unconnected-(PD3-Pad13)") (class "Default")
      (node (ref "PD3") (pin "13") (pinfunction "13_13") (pintype "passive"))
    )
    (net (code "96") (name "unconnected-(PD3-Pad14)") (class "Default")
      (node (ref "PD3") (pin "14") (pinfunction "14_14") (pintype "passive"))
    )
    (net (code "97") (name "unconnected-(PD3-Pad15)") (class "Default")
      (node (ref "PD3") (pin "15") (pinfunction "15_15") (pintype "passive"))
    )
    (net (code "98") (name "unconnected-(PD3-Pad16)") (class "Default")
      (node (ref "PD3") (pin "16") (pinfunction "16_16") (pintype "passive"))
    )
    (net (code "99") (name "unconnected-(PD3-Pad17)") (class "Default")
      (node (ref "PD3") (pin "17") (pinfunction "17_17") (pintype "passive"))
    )
    (net (code "100") (name "unconnected-(PD3-Pad18)") (class "Default")
      (node (ref "PD3") (pin "18") (pinfunction "18_18") (pintype "passive"))
    )
    (net (code "101") (name "unconnected-(PD3-Pad19)") (class "Default")
      (node (ref "PD3") (pin "19") (pinfunction "19_19") (pintype "passive"))
    )
    (net (code "102") (name "unconnected-(PD3-Pad20)") (class "Default")
      (node (ref "PD3") (pin "20") (pinfunction "20_20") (pintype "passive"))
    )
    (net (code "103") (name "unconnected-(SW2-IN2-Pad5)") (class "Default")
      (node (ref "SW2") (pin "5") (pinfunction "IN2_5") (pintype "passive"))
    )
    (net (code "104") (name "unconnected-(SW2-IN3-Pad6)") (class "Default")
      (node (ref "SW2") (pin "6") (pinfunction "IN3_6") (pintype "passive"))
    )
    (net (code "105") (name "unconnected-(SW2-OUT2-Pad2)") (class "Default")
      (node (ref "SW2") (pin "2") (pinfunction "OUT2_2") (pintype "passive"))
    )
    (net (code "106") (name "unconnected-(SW2-OUT3-Pad3)") (class "Default")
      (node (ref "SW2") (pin "3") (pinfunction "OUT3_3") (pintype "passive"))
    )
    (net (code "107") (name "unconnected-(U1-PA0-Pad10)") (class "Default")
      (node (ref "U1") (pin "10") (pinfunction "PA0_10") (pintype "passive"))
    )
    (net (code "108") (name "unconnected-(U1-PA1-Pad11)") (class "Default")
      (node (ref "U1") (pin "11") (pinfunction "PA1_11") (pintype "passive"))
    )
    (net (code "109") (name "unconnected-(U1-PA2-Pad12)") (class "Default")
      (node (ref "U1") (pin "12") (pinfunction "PA2_12") (pintype "passive"))
    )
    (net (code "110") (name "unconnected-(U1-PA3-Pad13)") (class "Default")
      (node (ref "U1") (pin "13") (pinfunction "PA3_13") (pintype "passive"))
    )
    (net (code "111") (name "unconnected-(U1-PA4-Pad14)") (class "Default")
      (node (ref "U1") (pin "14") (pinfunction "PA4_14") (pintype "passive"))
    )
    (net (code "112") (name "unconnected-(U1-PA6-Pad16)") (class "Default")
      (node (ref "U1") (pin "16") (pinfunction "PA6_16") (pintype "passive"))
    )
    (net (code "113") (name "unconnected-(U1-PA8-Pad29)") (class "Default")
      (node (ref "U1") (pin "29") (pinfunction "PA8_29") (pintype "passive"))
    )
    (net (code "114") (name "unconnected-(U1-PB0-Pad18)") (class "Default")
      (node (ref "U1") (pin "18") (pinfunction "PB0_18") (pintype "passive"))
    )
    (net (code "115") (name "unconnected-(U1-PB1-Pad19)") (class "Default")
      (node (ref "U1") (pin "19") (pinfunction "PB1_19") (pintype "passive"))
    )
    (net (code "116") (name "unconnected-(U1-PB10-Pad21)") (class "Default")
      (node (ref "U1") (pin "21") (pinfunction "PB10_21") (pintype "passive"))
    )
    (net (code "117") (name "unconnected-(U1-PB11-Pad22)") (class "Default")
      (node (ref "U1") (pin "22") (pinfunction "PB11_22") (pintype "passive"))
    )
    (net (code "118") (name "unconnected-(U1-PB12-Pad25)") (class "Default")
      (node (ref "U1") (pin "25") (pinfunction "PB12_25") (pintype "passive"))
    )
    (net (code "119") (name "unconnected-(U1-PB13-Pad26)") (class "Default")
      (node (ref "U1") (pin "26") (pinfunction "PB13_26") (pintype "passive"))
    )
    (net (code "120") (name "unconnected-(U1-PB14-Pad27)") (class "Default")
      (node (ref "U1") (pin "27") (pinfunction "PB14_27") (pintype "passive"))
    )
    (net (code "121") (name "unconnected-(U1-PB15-Pad28)") (class "Default")
      (node (ref "U1") (pin "28") (pinfunction "PB15_28") (pintype "passive"))
    )
    (net (code "122") (name "unconnected-(U1-VBAT-Pad1)") (class "Default")
      (node (ref "U1") (pin "1") (pinfunction "VBAT_1") (pintype "passive"))
    )
    (net (code "123") (name "unconnected-(U1-VDD_2-Pad36)") (class "Default")
      (node (ref "U1") (pin "36") (pinfunction "VDD_2_36") (pintype "passive"))
    )
    (net (code "124") (name "unconnected-(U1-VSSA-Pad8)") (class "Default")
      (node (ref "U1") (pin "8") (pinfunction "VSSA_8") (pintype "passive"))
    )
    (net (code "125") (name "unconnected-(U1-VSS_2-Pad35)") (class "Default")
      (node (ref "U1") (pin "35") (pinfunction "VSS_2_35") (pintype "passive"))
    )
    (net (code "126") (name "unconnected-(U1-VSS_3-Pad47)") (class "Default")
      (node (ref "U1") (pin "47") (pinfunction "VSS_3_47") (pintype "passive"))
    )
    (net (code "127") (name "unconnected-(USB1-D+-PadA6)") (class "Default")
      (node (ref "USB1") (pin "A6") (pinfunction "D+_A6") (pintype "passive"))
    )
    (net (code "128") (name "unconnected-(USB1-D+-PadB6)") (class "Default")
      (node (ref "USB1") (pin "B6") (pinfunction "D+_B6") (pintype "passive"))
    )
    (net (code "129") (name "unconnected-(USB1-D--PadA7)") (class "Default")
      (node (ref "USB1") (pin "A7") (pinfunction "D-_A7") (pintype "passive"))
    )
    (net (code "130") (name "unconnected-(USB1-D--PadB7)") (class "Default")
      (node (ref "USB1") (pin "B7") (pinfunction "D-_B7") (pintype "passive"))
    )
    (net (code "131") (name "unconnected-(USB1-RX1+-PadB11)") (class "Default")
      (node (ref "USB1") (pin "B11") (pinfunction "RX1+_B11") (pintype "passive"))
    )
    (net (code "132") (name "unconnected-(USB1-RX1--PadB10)") (class "Default")
      (node (ref "USB1") (pin "B10") (pinfunction "RX1-_B10") (pintype "passive"))
    )
    (net (code "133") (name "unconnected-(USB1-RX2+-PadA11)") (class "Default")
      (node (ref "USB1") (pin "A11") (pinfunction "RX2+_A11") (pintype "passive"))
    )
    (net (code "134") (name "unconnected-(USB1-RX2--PadA10)") (class "Default")
      (node (ref "USB1") (pin "A10") (pinfunction "RX2-_A10") (pintype "passive"))
    )
    (net (code "135") (name "unconnected-(USB1-SBU1-PadA8)") (class "Default")
      (node (ref "USB1") (pin "A8") (pinfunction "SBU1_A8") (pintype "passive"))
    )
    (net (code "136") (name "unconnected-(USB1-SBU2-PadB8)") (class "Default")
      (node (ref "USB1") (pin "B8") (pinfunction "SBU2_B8") (pintype "passive"))
    )
    (net (code "137") (name "unconnected-(USB1-TX1+-PadA2)") (class "Default")
      (node (ref "USB1") (pin "A2") (pinfunction "TX1+_A2") (pintype "passive"))
    )
    (net (code "138") (name "unconnected-(USB1-TX1--PadA3)") (class "Default")
      (node (ref "USB1") (pin "A3") (pinfunction "TX1-_A3") (pintype "passive"))
    )
    (net (code "139") (name "unconnected-(USB1-TX2+-PadB2)") (class "Default")
      (node (ref "USB1") (pin "B2") (pinfunction "TX2+_B2") (pintype "passive"))
    )
    (net (code "140") (name "unconnected-(USB1-TX2--PadB3)") (class "Default")
      (node (ref "USB1") (pin "B3") (pinfunction "TX2-_B3") (pintype "passive"))
    )
  )
)
